# LEDSequencer.net
KiCad netlist of a schematic drawn in Altium Designer
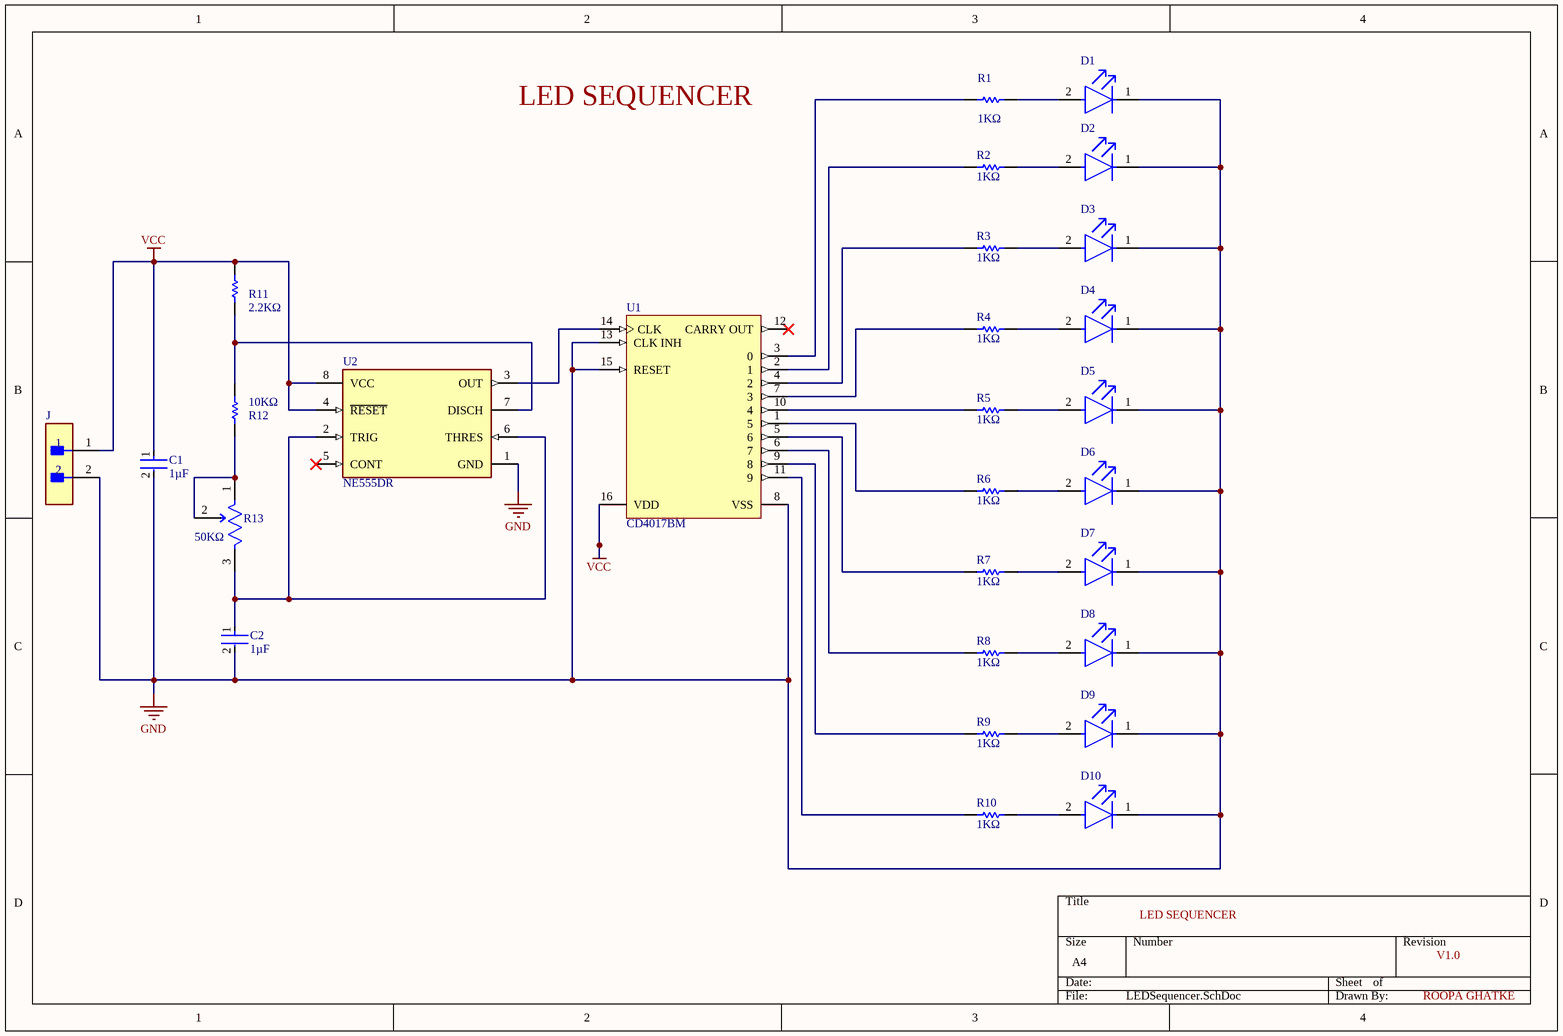
[diagram p0: LEDSequencer.SchDoc]

(export (version "E")
  (design (tool "Eeschema 10.0.6"))
  (components
    (comp (ref "C1")
      (value "1µF")
      (footprint "FP-GCM21B-0_15-IPC_C")
      (description "Ceramic Capacitor for Automotive 1uF ±10% 50VDC X7R 0805 Embossed T/R")
      (fields (field (name "TOLERANCE") "10%"))
      (libsource (lib "Altium Content Vault") (part "02cd4be3c70576c341d710602a673aa"))
    )
    (comp (ref "C2")
      (value "1µF")
      (footprint "FP-GCM21B-0_15-IPC_C")
      (description "Ceramic Capacitor for Automotive 1uF ±10% 50VDC X7R 0805 Embossed T/R")
      (fields (field (name "TOLERANCE") "10%"))
      (libsource (lib "Altium Content Vault") (part "02cd4be3c70576c341d710602a673aa"))
    )
    (comp (ref "D1")
      (value "HLMP-1301")
      (footprint "FP-HLMP-1301-MFG")
      (description "LED RED DIFFUSED T-1 T/H")
      (fields
        (field (name "OCTOPART") "https://octopart.com/hlmp-1301-broadcom-71130345")
        (field (name "MANUFACTURER") "Broadcom")
      )
      (libsource (lib "Altium Content Vault") (part "8706943c75ba83719d021d2fdc84c58"))
    )
    (comp (ref "D2")
      (value "HLMP-1301")
      (footprint "FP-HLMP-1301-MFG")
      (description "LED RED DIFFUSED T-1 T/H")
      (fields
        (field (name "OCTOPART") "https://octopart.com/hlmp-1301-broadcom-71130345")
        (field (name "MANUFACTURER") "Broadcom")
      )
      (libsource (lib "Altium Content Vault") (part "8706943c75ba83719d021d2fdc84c58"))
    )
    (comp (ref "D3")
      (value "HLMP-1301")
      (footprint "FP-HLMP-1301-MFG")
      (description "LED RED DIFFUSED T-1 T/H")
      (fields
        (field (name "OCTOPART") "https://octopart.com/hlmp-1301-broadcom-71130345")
        (field (name "MANUFACTURER") "Broadcom")
      )
      (libsource (lib "Altium Content Vault") (part "8706943c75ba83719d021d2fdc84c58"))
    )
    (comp (ref "D4")
      (value "HLMP-1301")
      (footprint "FP-HLMP-1301-MFG")
      (description "LED RED DIFFUSED T-1 T/H")
      (fields
        (field (name "OCTOPART") "https://octopart.com/hlmp-1301-broadcom-71130345")
        (field (name "MANUFACTURER") "Broadcom")
      )
      (libsource (lib "Altium Content Vault") (part "8706943c75ba83719d021d2fdc84c58"))
    )
    (comp (ref "D5")
      (value "HLMP-1301")
      (footprint "FP-HLMP-1301-MFG")
      (description "LED RED DIFFUSED T-1 T/H")
      (fields
        (field (name "OCTOPART") "https://octopart.com/hlmp-1301-broadcom-71130345")
        (field (name "MANUFACTURER") "Broadcom")
      )
      (libsource (lib "Altium Content Vault") (part "8706943c75ba83719d021d2fdc84c58"))
    )
    (comp (ref "D6")
      (value "HLMP-1301")
      (footprint "FP-HLMP-1301-MFG")
      (description "LED RED DIFFUSED T-1 T/H")
      (fields
        (field (name "OCTOPART") "https://octopart.com/hlmp-1301-broadcom-71130345")
        (field (name "MANUFACTURER") "Broadcom")
      )
      (libsource (lib "Altium Content Vault") (part "8706943c75ba83719d021d2fdc84c58"))
    )
    (comp (ref "D7")
      (value "HLMP-1301")
      (footprint "FP-HLMP-1301-MFG")
      (description "LED RED DIFFUSED T-1 T/H")
      (fields
        (field (name "OCTOPART") "https://octopart.com/hlmp-1301-broadcom-71130345")
        (field (name "MANUFACTURER") "Broadcom")
      )
      (libsource (lib "Altium Content Vault") (part "8706943c75ba83719d021d2fdc84c58"))
    )
    (comp (ref "D8")
      (value "HLMP-1301")
      (footprint "FP-HLMP-1301-MFG")
      (description "LED RED DIFFUSED T-1 T/H")
      (fields
        (field (name "OCTOPART") "https://octopart.com/hlmp-1301-broadcom-71130345")
        (field (name "MANUFACTURER") "Broadcom")
      )
      (libsource (lib "Altium Content Vault") (part "8706943c75ba83719d021d2fdc84c58"))
    )
    (comp (ref "D9")
      (value "HLMP-1301")
      (footprint "FP-HLMP-1301-MFG")
      (description "LED RED DIFFUSED T-1 T/H")
      (fields
        (field (name "OCTOPART") "https://octopart.com/hlmp-1301-broadcom-71130345")
        (field (name "MANUFACTURER") "Broadcom")
      )
      (libsource (lib "Altium Content Vault") (part "8706943c75ba83719d021d2fdc84c58"))
    )
    (comp (ref "D10")
      (value "HLMP-1301")
      (footprint "FP-HLMP-1301-MFG")
      (description "LED RED DIFFUSED T-1 T/H")
      (fields
        (field (name "OCTOPART") "https://octopart.com/hlmp-1301-broadcom-71130345")
        (field (name "MANUFACTURER") "Broadcom")
      )
      (libsource (lib "Altium Content Vault") (part "8706943c75ba83719d021d2fdc84c58"))
    )
    (comp (ref "J")
      (value "M20-9990245")
      (footprint "FP-M20-9990245-MFG")
      (description "CONN HEADER VERT 2POS 2.54MM")
      (fields (field (name "VOLTAGE") "50V"))
      (libsource (lib "Altium Content Vault") (part "3bc925449376181038e59eaffc5286c"))
    )
    (comp (ref "R1")
      (value "1KΩ")
      (footprint "RESC2013X60X35ML10T20")
      (description "Chip Resistor, 1 KOhm, +/- 1%, 125 mW, -55 to 155 degC, 0805 (2012 Metric), RoHS, Tape and Reel")
      (fields (field (name "TOLERANCE") "1%") (field (name "MANUFACTURER") "Yageo"))
      (libsource (lib "Altium Content Vault") (part "RES-2"))
    )
    (comp (ref "R2")
      (value "1KΩ")
      (footprint "RESC2013X60X35ML10T20")
      (description "Chip Resistor, 1 KOhm, +/- 1%, 125 mW, -55 to 155 degC, 0805 (2012 Metric), RoHS, Tape and Reel")
      (fields (field (name "TOLERANCE") "1%") (field (name "MANUFACTURER") "Yageo"))
      (libsource (lib "Altium Content Vault") (part "RES-2"))
    )
    (comp (ref "R3")
      (value "1KΩ")
      (footprint "RESC2013X60X35ML10T20")
      (description "Chip Resistor, 1 KOhm, +/- 1%, 125 mW, -55 to 155 degC, 0805 (2012 Metric), RoHS, Tape and Reel")
      (fields (field (name "TOLERANCE") "1%") (field (name "MANUFACTURER") "Yageo"))
      (libsource (lib "Altium Content Vault") (part "RES-2"))
    )
    (comp (ref "R4")
      (value "1KΩ")
      (footprint "RESC2013X60X35ML10T20")
      (description "Chip Resistor, 1 KOhm, +/- 1%, 125 mW, -55 to 155 degC, 0805 (2012 Metric), RoHS, Tape and Reel")
      (fields (field (name "TOLERANCE") "1%") (field (name "MANUFACTURER") "Yageo"))
      (libsource (lib "Altium Content Vault") (part "RES-2"))
    )
    (comp (ref "R5")
      (value "1KΩ")
      (footprint "RESC2013X60X35ML10T20")
      (description "Chip Resistor, 1 KOhm, +/- 1%, 125 mW, -55 to 155 degC, 0805 (2012 Metric), RoHS, Tape and Reel")
      (fields (field (name "TOLERANCE") "1%") (field (name "MANUFACTURER") "Yageo"))
      (libsource (lib "Altium Content Vault") (part "RES-2"))
    )
    (comp (ref "R6")
      (value "1KΩ")
      (footprint "RESC2013X60X35ML10T20")
      (description "Chip Resistor, 1 KOhm, +/- 1%, 125 mW, -55 to 155 degC, 0805 (2012 Metric), RoHS, Tape and Reel")
      (fields (field (name "TOLERANCE") "1%") (field (name "MANUFACTURER") "Yageo"))
      (libsource (lib "Altium Content Vault") (part "RES-2"))
    )
    (comp (ref "R7")
      (value "1KΩ")
      (footprint "RESC2013X60X35ML10T20")
      (description "Chip Resistor, 1 KOhm, +/- 1%, 125 mW, -55 to 155 degC, 0805 (2012 Metric), RoHS, Tape and Reel")
      (fields (field (name "TOLERANCE") "1%") (field (name "MANUFACTURER") "Yageo"))
      (libsource (lib "Altium Content Vault") (part "RES-2"))
    )
    (comp (ref "R8")
      (value "1KΩ")
      (footprint "RESC2013X60X35ML10T20")
      (description "Chip Resistor, 1 KOhm, +/- 1%, 125 mW, -55 to 155 degC, 0805 (2012 Metric), RoHS, Tape and Reel")
      (fields (field (name "TOLERANCE") "1%") (field (name "MANUFACTURER") "Yageo"))
      (libsource (lib "Altium Content Vault") (part "RES-2"))
    )
    (comp (ref "R9")
      (value "1KΩ")
      (footprint "RESC2013X60X35ML10T20")
      (description "Chip Resistor, 1 KOhm, +/- 1%, 125 mW, -55 to 155 degC, 0805 (2012 Metric), RoHS, Tape and Reel")
      (fields (field (name "TOLERANCE") "1%") (field (name "MANUFACTURER") "Yageo"))
      (libsource (lib "Altium Content Vault") (part "RES-2"))
    )
    (comp (ref "R10")
      (value "1KΩ")
      (footprint "RESC2013X60X35ML10T20")
      (description "Chip Resistor, 1 KOhm, +/- 1%, 125 mW, -55 to 155 degC, 0805 (2012 Metric), RoHS, Tape and Reel")
      (fields (field (name "TOLERANCE") "1%") (field (name "MANUFACTURER") "Yageo"))
      (libsource (lib "Altium Content Vault") (part "RES-2"))
    )
    (comp (ref "R11")
      (value "2.2KΩ")
      (footprint "RESC2013X60X35ML10T20")
      (description "Chip Resistor, 1 KOhm, +/- 1%, 125 mW, -55 to 155 degC, 0805 (2012 Metric), RoHS, Tape and Reel")
      (fields (field (name "TOLERANCE") "1%") (field (name "MANUFACTURER") "Yageo"))
      (libsource (lib "Altium Content Vault") (part "RES-2"))
    )
    (comp (ref "R12")
      (value "10KΩ")
      (footprint "RESC2013X60X35ML10T20")
      (description "Chip Resistor, 1 KOhm, +/- 1%, 125 mW, -55 to 155 degC, 0805 (2012 Metric), RoHS, Tape and Reel")
      (fields (field (name "TOLERANCE") "1%") (field (name "MANUFACTURER") "Yageo"))
      (libsource (lib "Altium Content Vault") (part "RES-2"))
    )
    (comp (ref "R13")
      (value "50KΩ")
      (footprint "FP-3386P-MFG")
      (description "TRIMMER 100K OHM 0.5W PC PIN TOP")
      (fields (field (name "TOLERANCE") "10%"))
      (libsource (lib "Altium Content Vault") (part "13357d81287629c2fd191d242cfa50c"))
    )
    (comp (ref "U1")
      (value "CD4017BM")
      (footprint "D0016A_N")
      (description "CMOS Decade Counter with 10 Decoded Outputs, D0016A, TUBE")
      (fields
        (field (name "GENERIC PART NUMBER") "CD4017B")
        (field (name "MANUFACTURER") "Texas Instruments")
      )
      (libsource (lib "Altium Content Vault") (part "TI-CD4017B-16"))
    )
    (comp (ref "U2")
      (value "NE555DR")
      (footprint "FP-D0008A-IPC_A")
      (description "IC OSC SGL TIMER 100KHZ 8-SOIC")
      (libsource (lib "Altium Content Vault") (part "a29bba90211dec1890110b94dad7d53"))
    )
  )
  (nets
    (net (code "1") (name "GND") (class "Default")
      (node (ref "C1") (pin "2") (pinfunction "2_2") (pintype "passive"))
      (node (ref "C2") (pin "2") (pinfunction "2_2") (pintype "passive"))
      (node (ref "D1") (pin "1") (pinfunction "C_1") (pintype "passive"))
      (node (ref "D10") (pin "1") (pinfunction "C_1") (pintype "passive"))
      (node (ref "D2") (pin "1") (pinfunction "C_1") (pintype "passive"))
      (node (ref "D3") (pin "1") (pinfunction "C_1") (pintype "passive"))
      (node (ref "D4") (pin "1") (pinfunction "C_1") (pintype "passive"))
      (node (ref "D5") (pin "1") (pinfunction "C_1") (pintype "passive"))
      (node (ref "D6") (pin "1") (pinfunction "C_1") (pintype "passive"))
      (node (ref "D7") (pin "1") (pinfunction "C_1") (pintype "passive"))
      (node (ref "D8") (pin "1") (pinfunction "C_1") (pintype "passive"))
      (node (ref "D9") (pin "1") (pinfunction "C_1") (pintype "passive"))
      (node (ref "J") (pin "2") (pinfunction "2_2") (pintype "passive"))
      (node (ref "U1") (pin "13") (pinfunction "CLK_INH_13") (pintype "input"))
      (node (ref "U1") (pin "15") (pinfunction "RESET_15") (pintype "input"))
      (node (ref "U1") (pin "8") (pinfunction "VSS_8") (pintype "power_in"))
      (node (ref "U2") (pin "1") (pinfunction "GND_1") (pintype "power_in"))
    )
    (net (code "2") (name "Net-(D1-A)") (class "Default")
      (node (ref "D1") (pin "2") (pinfunction "A_2") (pintype "passive"))
      (node (ref "R1") (pin "2") (pinfunction "2_2") (pintype "passive"))
    )
    (net (code "3") (name "Net-(D2-A)") (class "Default")
      (node (ref "D2") (pin "2") (pinfunction "A_2") (pintype "passive"))
      (node (ref "R2") (pin "2") (pinfunction "2_2") (pintype "passive"))
    )
    (net (code "4") (name "Net-(D3-A)") (class "Default")
      (node (ref "D3") (pin "2") (pinfunction "A_2") (pintype "passive"))
      (node (ref "R3") (pin "2") (pinfunction "2_2") (pintype "passive"))
    )
    (net (code "5") (name "Net-(D4-A)") (class "Default")
      (node (ref "D4") (pin "2") (pinfunction "A_2") (pintype "passive"))
      (node (ref "R4") (pin "2") (pinfunction "2_2") (pintype "passive"))
    )
    (net (code "6") (name "Net-(D5-A)") (class "Default")
      (node (ref "D5") (pin "2") (pinfunction "A_2") (pintype "passive"))
      (node (ref "R5") (pin "2") (pinfunction "2_2") (pintype "passive"))
    )
    (net (code "7") (name "Net-(D6-A)") (class "Default")
      (node (ref "D6") (pin "2") (pinfunction "A_2") (pintype "passive"))
      (node (ref "R6") (pin "2") (pinfunction "2_2") (pintype "passive"))
    )
    (net (code "8") (name "Net-(D7-A)") (class "Default")
      (node (ref "D7") (pin "2") (pinfunction "A_2") (pintype "passive"))
      (node (ref "R7") (pin "2") (pinfunction "2_2") (pintype "passive"))
    )
    (net (code "9") (name "Net-(D8-A)") (class "Default")
      (node (ref "D8") (pin "2") (pinfunction "A_2") (pintype "passive"))
      (node (ref "R8") (pin "2") (pinfunction "2_2") (pintype "passive"))
    )
    (net (code "10") (name "Net-(D9-A)") (class "Default")
      (node (ref "D9") (pin "2") (pinfunction "A_2") (pintype "passive"))
      (node (ref "R9") (pin "2") (pinfunction "2_2") (pintype "passive"))
    )
    (net (code "11") (name "Net-(D10-A)") (class "Default")
      (node (ref "D10") (pin "2") (pinfunction "A_2") (pintype "passive"))
      (node (ref "R10") (pin "2") (pinfunction "2_2") (pintype "passive"))
    )
    (net (code "12") (name "Net-(R13-CCW)") (class "Default")
      (node (ref "R12") (pin "1") (pinfunction "1_1") (pintype "passive"))
      (node (ref "R13") (pin "1") (pinfunction "CCW_1") (pintype "passive"))
      (node (ref "R13") (pin "2") (pinfunction "WIPER_2") (pintype "passive"))
    )
    (net (code "13") (name "Net-(R13-CW)") (class "Default")
      (node (ref "C2") (pin "1") (pinfunction "1_1") (pintype "passive"))
      (node (ref "R13") (pin "3") (pinfunction "CW_3") (pintype "passive"))
      (node (ref "U2") (pin "2") (pinfunction "TRIG_2") (pintype "input"))
      (node (ref "U2") (pin "6") (pinfunction "THRES_6") (pintype "input"))
    )
    (net (code "14") (name "Net-(U1-0)") (class "Default")
      (node (ref "R1") (pin "1") (pinfunction "1_1") (pintype "passive"))
      (node (ref "U1") (pin "3") (pinfunction "0_3") (pintype "output"))
    )
    (net (code "15") (name "Net-(U1-1)") (class "Default")
      (node (ref "R2") (pin "1") (pinfunction "1_1") (pintype "passive"))
      (node (ref "U1") (pin "2") (pinfunction "1_2") (pintype "output"))
    )
    (net (code "16") (name "Net-(U1-2)") (class "Default")
      (node (ref "R3") (pin "1") (pinfunction "1_1") (pintype "passive"))
      (node (ref "U1") (pin "4") (pinfunction "2_4") (pintype "output"))
    )
    (net (code "17") (name "Net-(U1-3)") (class "Default")
      (node (ref "R4") (pin "1") (pinfunction "1_1") (pintype "passive"))
      (node (ref "U1") (pin "7") (pinfunction "3_7") (pintype "output"))
    )
    (net (code "18") (name "Net-(U1-4)") (class "Default")
      (node (ref "R5") (pin "1") (pinfunction "1_1") (pintype "passive"))
      (node (ref "U1") (pin "10") (pinfunction "4_10") (pintype "output"))
    )
    (net (code "19") (name "Net-(U1-5)") (class "Default")
      (node (ref "R6") (pin "1") (pinfunction "1_1") (pintype "passive"))
      (node (ref "U1") (pin "1") (pinfunction "5_1") (pintype "output"))
    )
    (net (code "20") (name "Net-(U1-6)") (class "Default")
      (node (ref "R7") (pin "1") (pinfunction "1_1") (pintype "passive"))
      (node (ref "U1") (pin "5") (pinfunction "6_5") (pintype "output"))
    )
    (net (code "21") (name "Net-(U1-7)") (class "Default")
      (node (ref "R8") (pin "1") (pinfunction "1_1") (pintype "passive"))
      (node (ref "U1") (pin "6") (pinfunction "7_6") (pintype "output"))
    )
    (net (code "22") (name "Net-(U1-8)") (class "Default")
      (node (ref "R9") (pin "1") (pinfunction "1_1") (pintype "passive"))
      (node (ref "U1") (pin "9") (pinfunction "8_9") (pintype "output"))
    )
    (net (code "23") (name "Net-(U1-9)") (class "Default")
      (node (ref "R10") (pin "1") (pinfunction "1_1") (pintype "passive"))
      (node (ref "U1") (pin "11") (pinfunction "9_11") (pintype "output"))
    )
    (net (code "24") (name "Net-(U1-CLK)") (class "Default")
      (node (ref "U1") (pin "14") (pinfunction "CLK_14") (pintype "input"))
      (node (ref "U2") (pin "3") (pinfunction "OUT_3") (pintype "output"))
    )
    (net (code "25") (name "Net-(U2-DISCH)") (class "Default")
      (node (ref "R11") (pin "1") (pinfunction "1_1") (pintype "passive"))
      (node (ref "R12") (pin "2") (pinfunction "2_2") (pintype "passive"))
      (node (ref "U2") (pin "7") (pinfunction "DISCH_7") (pintype "open_collector"))
    )
    (net (code "26") (name "VCC") (class "Default")
      (node (ref "C1") (pin "1") (pinfunction "1_1") (pintype "passive"))
      (node (ref "J") (pin "1") (pinfunction "1_1") (pintype "passive"))
      (node (ref "R11") (pin "2") (pinfunction "2_2") (pintype "passive"))
      (node (ref "U1") (pin "16") (pinfunction "VDD_16") (pintype "power_in"))
      (node (ref "U2") (pin "4") (pinfunction "~{RESET}_4") (pintype "input"))
      (node (ref "U2") (pin "8") (pinfunction "VCC_8") (pintype "power_in"))
    )
    (net (code "27") (name "unconnected-(U1-CARRY_OUT-Pad12)") (class "Default")
      (node (ref "U1") (pin "12") (pinfunction "CARRY_OUT_12") (pintype "output+no_connect"))
    )
    (net (code "28") (name "unconnected-(U2-CONT-Pad5)") (class "Default")
      (node (ref "U2") (pin "5") (pinfunction "CONT_5") (pintype "input+no_connect"))
    )
  )
)
